# atmega_midi_x0x_heart.net
KiCad netlist of a schematic drawn in EAGLE
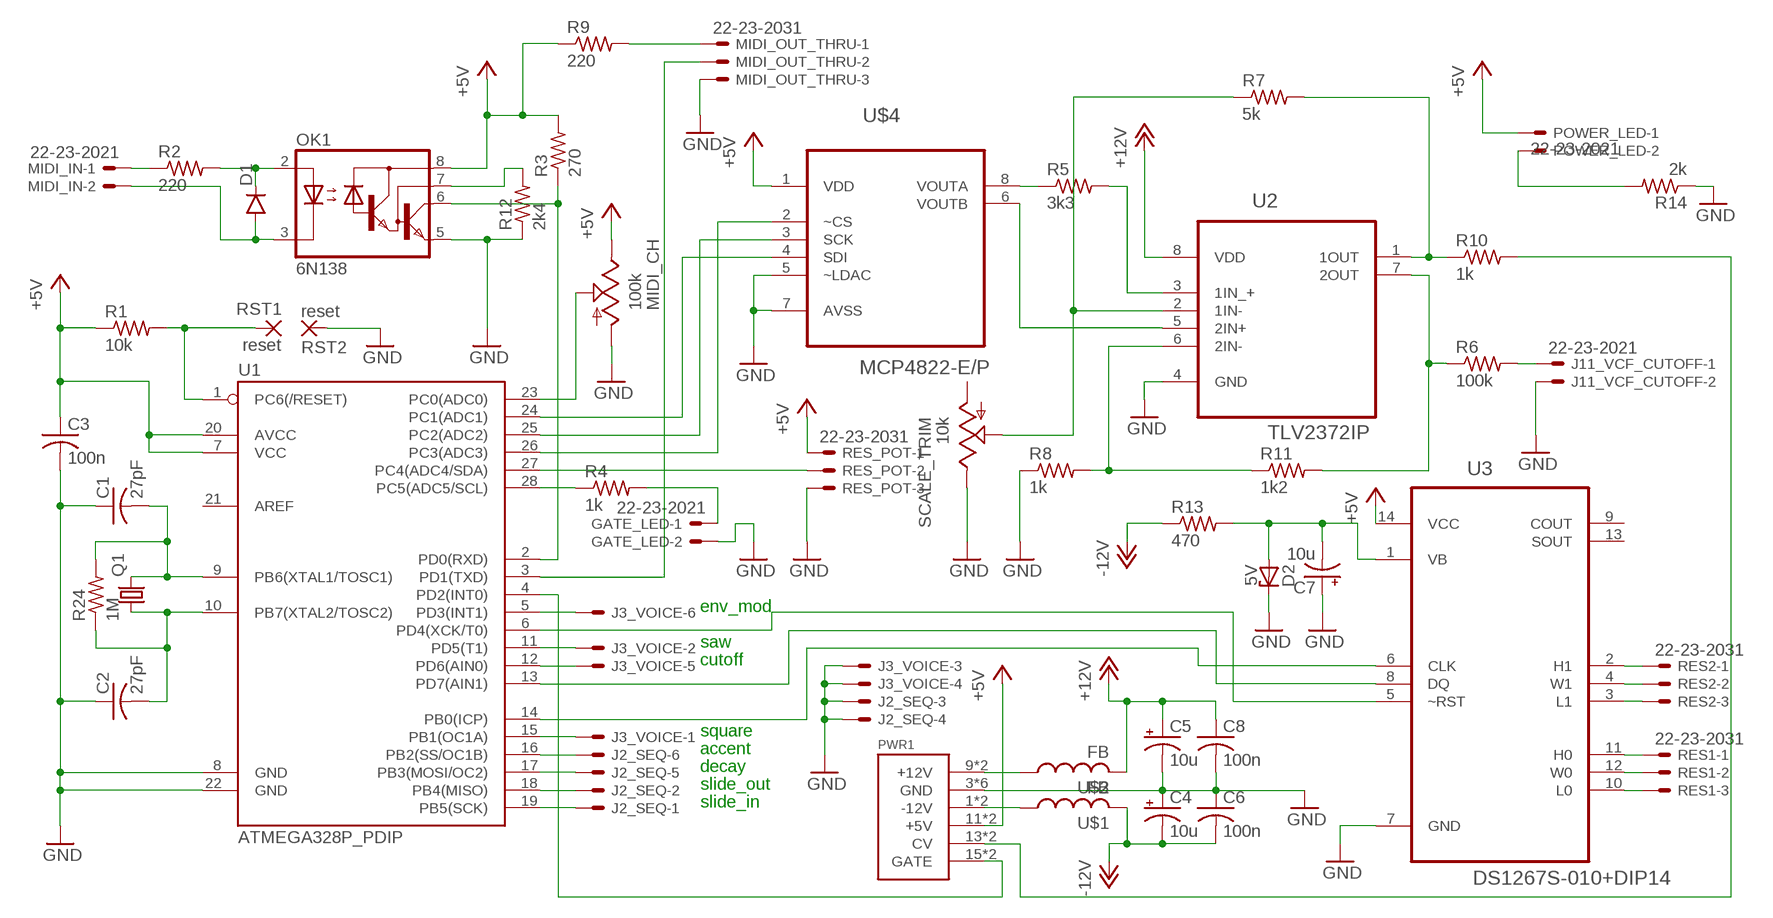
[diagram p0: schematic, sheet 1]

(export (version "E")
  (design (tool "Eeschema 10.0.6"))
  (components
    (comp (ref "C1")
      (value "27pF")
      (footprint "eagle-import:C050-024X044")
      (libsource (lib "eagle-import") (part "C-US050-024X044"))
    )
    (comp (ref "C2")
      (value "27pF")
      (footprint "eagle-import:C050-024X044")
      (libsource (lib "eagle-import") (part "C-US050-024X044"))
    )
    (comp (ref "C3")
      (value "100n")
      (footprint "eagle-import:C050-024X044")
      (libsource (lib "eagle-import") (part "C-US050-024X044"))
    )
    (comp (ref "C4")
      (value "10u")
      (footprint "eagle-import:B45181A")
      (libsource (lib "eagle-import") (part "CPOL-USB45181A"))
    )
    (comp (ref "C5")
      (value "10u")
      (footprint "eagle-import:B45181A")
      (libsource (lib "eagle-import") (part "CPOL-USB45181A"))
    )
    (comp (ref "C6")
      (value "100n")
      (footprint "eagle-import:C050-024X044")
      (libsource (lib "eagle-import") (part "C-US050-024X044"))
    )
    (comp (ref "C7")
      (value "10u")
      (footprint "eagle-import:B45181B")
      (libsource (lib "eagle-import") (part "CPOL-USB45181B"))
    )
    (comp (ref "C8")
      (value "100n")
      (footprint "eagle-import:C050-024X044")
      (libsource (lib "eagle-import") (part "C-US050-024X044"))
    )
    (comp (ref "D1")
      (value "DIODE1N4148")
      (footprint "eagle-import:DIODE-1N4148")
      (libsource (lib "eagle-import") (part "DIODE1N4148"))
    )
    (comp (ref "D2")
      (value "5V")
      (footprint "eagle-import:DO35Z10")
      (libsource (lib "eagle-import") (part "ZENER-DIODEDO35Z10"))
    )
    (comp (ref "GATE_LED")
      (value "22-23-2021")
      (footprint "eagle-import:22-23-2021")
      (fields (field (name "MF") "MOLEX"))
      (libsource (lib "eagle-import") (part "22-23-2021"))
    )
    (comp (ref "J2_SEQ")
      (value "22-23-2061")
      (footprint "eagle-import:22-23-2061")
      (fields (field (name "MF") "MOLEX"))
      (libsource (lib "eagle-import") (part "22-23-2061"))
    )
    (comp (ref "J3_VOICE")
      (value "22-23-2061")
      (footprint "eagle-import:22-23-2061")
      (fields (field (name "MF") "MOLEX"))
      (libsource (lib "eagle-import") (part "22-23-2061"))
    )
    (comp (ref "J11_VCF_CUTOFF")
      (value "22-23-2021")
      (footprint "eagle-import:22-23-2021")
      (fields (field (name "MF") "MOLEX"))
      (libsource (lib "eagle-import") (part "22-23-2021"))
    )
    (comp (ref "MIDI_CH")
      (value "100k")
      (footprint "eagle-import:B64W")
      (libsource (lib "eagle-import") (part "TRIM_US-B64W"))
    )
    (comp (ref "MIDI_IN")
      (value "22-23-2021")
      (footprint "eagle-import:22-23-2021")
      (fields (field (name "MF") "MOLEX"))
      (libsource (lib "eagle-import") (part "22-23-2021"))
    )
    (comp (ref "MIDI_OUT_THRU")
      (value "22-23-2031")
      (footprint "eagle-import:22-23-2031")
      (fields (field (name "MF") "MOLEX"))
      (libsource (lib "eagle-import") (part "22-23-2031"))
    )
    (comp (ref "OK1")
      (value "6N138")
      (footprint "eagle-import:DIL08")
      (fields (field (name "MF") "VISHAY/TELEFUNKEN"))
      (libsource (lib "eagle-import") (part "6N138"))
    )
    (comp (ref "POWER_LED")
      (value "22-23-2021")
      (footprint "eagle-import:22-23-2021")
      (fields (field (name "MF") "MOLEX"))
      (libsource (lib "eagle-import") (part "22-23-2021"))
    )
    (comp (ref "PWR1")
      (value "POWER")
      (footprint "eagle-import:POWER_16")
      (libsource (lib "eagle-import") (part "POWER"))
    )
    (comp (ref "Q1")
      (value "CRYSTALHC49S")
      (footprint "eagle-import:HC49_S")
      (libsource (lib "eagle-import") (part "CRYSTALHC49S"))
    )
    (comp (ref "R1")
      (value "10k")
      (footprint "eagle-import:0207_10")
      (libsource (lib "eagle-import") (part "R-US_0207/10"))
    )
    (comp (ref "R2")
      (value "220")
      (footprint "eagle-import:0207_10")
      (libsource (lib "eagle-import") (part "R-US_0207/10"))
    )
    (comp (ref "R3")
      (value "270")
      (footprint "eagle-import:0207_10")
      (libsource (lib "eagle-import") (part "R-US_0207/10"))
    )
    (comp (ref "R4")
      (value "1k")
      (footprint "eagle-import:0207_10")
      (libsource (lib "eagle-import") (part "R-US_0207/10"))
    )
    (comp (ref "R5")
      (value "3k3")
      (footprint "eagle-import:0207_10")
      (libsource (lib "eagle-import") (part "R-US_0207/10"))
    )
    (comp (ref "R6")
      (value "100k")
      (footprint "eagle-import:0207_10")
      (libsource (lib "eagle-import") (part "R-US_0207/10"))
    )
    (comp (ref "R7")
      (value "5k")
      (footprint "eagle-import:0207_10")
      (libsource (lib "eagle-import") (part "R-US_0207/10"))
    )
    (comp (ref "R8")
      (value "1k")
      (footprint "eagle-import:0207_10")
      (libsource (lib "eagle-import") (part "R-US_0207/10"))
    )
    (comp (ref "R9")
      (value "220")
      (footprint "eagle-import:0207_10")
      (libsource (lib "eagle-import") (part "R-US_0207/10"))
    )
    (comp (ref "R10")
      (value "1k")
      (footprint "eagle-import:0207_10")
      (libsource (lib "eagle-import") (part "R-US_0207/10"))
    )
    (comp (ref "R11")
      (value "1k2")
      (footprint "eagle-import:0207_10")
      (libsource (lib "eagle-import") (part "R-US_0207/10"))
    )
    (comp (ref "R12")
      (value "2k4")
      (footprint "eagle-import:0207_10")
      (libsource (lib "eagle-import") (part "R-US_0207/10"))
    )
    (comp (ref "R13")
      (value "470")
      (footprint "eagle-import:0207_10")
      (libsource (lib "eagle-import") (part "R-US_0207/10"))
    )
    (comp (ref "R14")
      (value "2k")
      (footprint "eagle-import:0207_10")
      (libsource (lib "eagle-import") (part "R-US_0207/10"))
    )
    (comp (ref "R24")
      (value "1M")
      (footprint "eagle-import:0207_10")
      (libsource (lib "eagle-import") (part "R-US_0207/10"))
    )
    (comp (ref "RES1")
      (value "22-23-2031")
      (footprint "eagle-import:22-23-2031")
      (fields (field (name "MF") "MOLEX"))
      (libsource (lib "eagle-import") (part "22-23-2031"))
    )
    (comp (ref "RES2")
      (value "22-23-2031")
      (footprint "eagle-import:22-23-2031")
      (fields (field (name "MF") "MOLEX"))
      (libsource (lib "eagle-import") (part "22-23-2031"))
    )
    (comp (ref "RES_POT")
      (value "22-23-2031")
      (footprint "eagle-import:22-23-2031")
      (fields (field (name "MF") "MOLEX"))
      (libsource (lib "eagle-import") (part "22-23-2031"))
    )
    (comp (ref "RST1")
      (value "reset")
      (footprint "eagle-import:2,54_0,9")
      (libsource (lib "eagle-import") (part "2,54/0,9"))
    )
    (comp (ref "RST2")
      (value "reset")
      (footprint "eagle-import:2,54_0,9")
      (libsource (lib "eagle-import") (part "2,54/0,9"))
    )
    (comp (ref "SCALE_TRIM")
      (value "10k")
      (footprint "eagle-import:B64W")
      (libsource (lib "eagle-import") (part "TRIM_US-B64W"))
    )
    (comp (ref "U$1") (value "FB") (footprint "eagle-import:FB") (libsource (lib "eagle-import") (part "FB")))
    (comp (ref "U$2") (value "FB") (footprint "eagle-import:FB") (libsource (lib "eagle-import") (part "FB")))
    (comp (ref "U$4")
      (value "MCP4822-E/P")
      (footprint "eagle-import:DIP254P762X432-8")
      (libsource (lib "eagle-import") (part "MCP4822-E/P"))
    )
    (comp (ref "U1")
      (value "ATMEGA328P_PDIP")
      (footprint "eagle-import:DIL28-3")
      (libsource (lib "eagle-import") (part "ATMEGA328P_PDIP"))
    )
    (comp (ref "U2")
      (value "TLV2372IP")
      (footprint "eagle-import:DIP254P762X508-8")
      (libsource (lib "eagle-import") (part "TLV2372IP"))
    )
    (comp (ref "U3")
      (value "DS1267S-010+DIP14")
      (footprint "eagle-import:DIP14")
      (libsource (lib "eagle-import") (part "DS1267S-010+DIP14"))
    )
  )
  (nets
    (net (code "1") (name "+5V") (class "Default")
      (node (ref "C3") (pin "1") (pinfunction "1_1") (pintype "passive"))
      (node (ref "MIDI_CH") (pin "E") (pinfunction "E_E") (pintype "passive"))
      (node (ref "OK1") (pin "8") (pinfunction "VCC_8") (pintype "passive"))
      (node (ref "POWER_LED") (pin "1") (pinfunction "S_1") (pintype "passive"))
      (node (ref "PWR1") (pin "11") (pinfunction "+5V_11") (pintype "bidirectional"))
      (node (ref "PWR1") (pin "12") (pinfunction "+5V_12") (pintype "bidirectional"))
      (node (ref "R1") (pin "1") (pinfunction "1_1") (pintype "passive"))
      (node (ref "R3") (pin "2") (pinfunction "2_2") (pintype "passive"))
      (node (ref "R9") (pin "1") (pinfunction "1_1") (pintype "passive"))
      (node (ref "RES_POT") (pin "1") (pinfunction "S_1") (pintype "passive"))
      (node (ref "U$4") (pin "1") (pinfunction "VDD_1") (pintype "power_in"))
      (node (ref "U1") (pin "20") (pinfunction "AVCC_20") (pintype "bidirectional"))
      (node (ref "U1") (pin "7") (pinfunction "VCC_7") (pintype "bidirectional"))
      (node (ref "U3") (pin "14") (pinfunction "VCC_14") (pintype "power_in"))
    )
    (net (code "2") (name "+12V") (class "Default")
      (node (ref "C5") (pin "+") (pinfunction "+_+") (pintype "passive"))
      (node (ref "C8") (pin "1") (pinfunction "1_1") (pintype "passive"))
      (node (ref "U$2") (pin "P$2") (pinfunction "2_P$2") (pintype "passive"))
      (node (ref "U2") (pin "8") (pinfunction "VDD_8") (pintype "power_in"))
    )
    (net (code "3") (name "-12V") (class "Default")
      (node (ref "C4") (pin "-") (pinfunction "-_-") (pintype "passive"))
      (node (ref "C6") (pin "2") (pinfunction "2_2") (pintype "passive"))
      (node (ref "R13") (pin "1") (pinfunction "1_1") (pintype "passive"))
      (node (ref "U$1") (pin "P$2") (pinfunction "2_P$2") (pintype "passive"))
    )
    (net (code "4") (name "GND") (class "Default")
      (node (ref "C1") (pin "1") (pinfunction "1_1") (pintype "passive"))
      (node (ref "C2") (pin "1") (pinfunction "1_1") (pintype "passive"))
      (node (ref "C3") (pin "2") (pinfunction "2_2") (pintype "passive"))
      (node (ref "C4") (pin "+") (pinfunction "+_+") (pintype "passive"))
      (node (ref "C5") (pin "-") (pinfunction "-_-") (pintype "passive"))
      (node (ref "C6") (pin "1") (pinfunction "1_1") (pintype "passive"))
      (node (ref "C7") (pin "+") (pinfunction "+_+") (pintype "passive"))
      (node (ref "C8") (pin "2") (pinfunction "2_2") (pintype "passive"))
      (node (ref "D2") (pin "C") (pinfunction "C_C") (pintype "passive"))
      (node (ref "GATE_LED") (pin "2") (pinfunction "S_2") (pintype "passive"))
      (node (ref "J11_VCF_CUTOFF") (pin "2") (pinfunction "S_2") (pintype "passive"))
      (node (ref "J2_SEQ") (pin "3") (pinfunction "S_3") (pintype "passive"))
      (node (ref "J2_SEQ") (pin "4") (pinfunction "S_4") (pintype "passive"))
      (node (ref "J3_VOICE") (pin "3") (pinfunction "S_3") (pintype "passive"))
      (node (ref "J3_VOICE") (pin "4") (pinfunction "S_4") (pintype "passive"))
      (node (ref "MIDI_CH") (pin "A") (pinfunction "A_A") (pintype "passive"))
      (node (ref "MIDI_OUT_THRU") (pin "3") (pinfunction "S_3") (pintype "passive"))
      (node (ref "OK1") (pin "5") (pinfunction "GND_5") (pintype "passive"))
      (node (ref "PWR1") (pin "3") (pinfunction "GND_3") (pintype "bidirectional"))
      (node (ref "PWR1") (pin "4") (pinfunction "GND_4") (pintype "bidirectional"))
      (node (ref "PWR1") (pin "5") (pinfunction "GND_5") (pintype "bidirectional"))
      (node (ref "PWR1") (pin "6") (pinfunction "GND_6") (pintype "bidirectional"))
      (node (ref "PWR1") (pin "7") (pinfunction "GND_7") (pintype "bidirectional"))
      (node (ref "PWR1") (pin "8") (pinfunction "GND_8") (pintype "bidirectional"))
      (node (ref "R12") (pin "1") (pinfunction "1_1") (pintype "passive"))
      (node (ref "R14") (pin "1") (pinfunction "1_1") (pintype "passive"))
      (node (ref "R8") (pin "1") (pinfunction "1_1") (pintype "passive"))
      (node (ref "RES_POT") (pin "3") (pinfunction "S_3") (pintype "passive"))
      (node (ref "RST2") (pin "1") (pinfunction "P_1") (pintype "passive"))
      (node (ref "SCALE_TRIM") (pin "E") (pinfunction "E_E") (pintype "passive"))
      (node (ref "U$4") (pin "5") (pinfunction "~{LDAC}_5") (pintype "input"))
      (node (ref "U$4") (pin "7") (pinfunction "AVSS_7") (pintype "passive"))
      (node (ref "U1") (pin "22") (pinfunction "GND_22") (pintype "bidirectional"))
      (node (ref "U1") (pin "8") (pinfunction "GND_8") (pintype "bidirectional"))
      (node (ref "U2") (pin "4") (pinfunction "GND_4") (pintype "passive"))
      (node (ref "U3") (pin "7") (pinfunction "GND_7") (pintype "passive"))
    )
    (net (code "5") (name "Net-(GATE_LEDA-S)") (class "Default")
      (node (ref "GATE_LED") (pin "1") (pinfunction "S_1") (pintype "passive"))
      (node (ref "R4") (pin "2") (pinfunction "2_2") (pintype "passive"))
    )
    (net (code "6") (name "Net-(J2_SEQA-S)") (class "Default")
      (node (ref "J2_SEQ") (pin "1") (pinfunction "S_1") (pintype "passive"))
      (node (ref "U1") (pin "19") (pinfunction "PB5(SCK)_19") (pintype "bidirectional"))
    )
    (net (code "7") (name "Net-(J2_SEQB-S)") (class "Default")
      (node (ref "J2_SEQ") (pin "2") (pinfunction "S_2") (pintype "passive"))
      (node (ref "U1") (pin "18") (pinfunction "PB4(MISO)_18") (pintype "bidirectional"))
    )
    (net (code "8") (name "Net-(J2_SEQE-S)") (class "Default")
      (node (ref "J2_SEQ") (pin "5") (pinfunction "S_5") (pintype "passive"))
      (node (ref "U1") (pin "17") (pinfunction "PB3(MOSI/OC2)_17") (pintype "bidirectional"))
    )
    (net (code "9") (name "Net-(J2_SEQF-S)") (class "Default")
      (node (ref "J2_SEQ") (pin "6") (pinfunction "S_6") (pintype "passive"))
      (node (ref "U1") (pin "16") (pinfunction "PB2(SS/OC1B)_16") (pintype "bidirectional"))
    )
    (net (code "10") (name "Net-(J3_VOICEA-S)") (class "Default")
      (node (ref "J3_VOICE") (pin "1") (pinfunction "S_1") (pintype "passive"))
      (node (ref "U1") (pin "15") (pinfunction "PB1(OC1A)_15") (pintype "bidirectional"))
    )
    (net (code "11") (name "Net-(J3_VOICEB-S)") (class "Default")
      (node (ref "J3_VOICE") (pin "2") (pinfunction "S_2") (pintype "passive"))
      (node (ref "U1") (pin "11") (pinfunction "PD5(T1)_11") (pintype "bidirectional"))
    )
    (net (code "12") (name "Net-(J3_VOICEE-S)") (class "Default")
      (node (ref "J3_VOICE") (pin "5") (pinfunction "S_5") (pintype "passive"))
      (node (ref "U1") (pin "12") (pinfunction "PD6(AIN0)_12") (pintype "bidirectional"))
    )
    (net (code "13") (name "Net-(J3_VOICEF-S)") (class "Default")
      (node (ref "J3_VOICE") (pin "6") (pinfunction "S_6") (pintype "passive"))
      (node (ref "U1") (pin "5") (pinfunction "PD3(INT1)_5") (pintype "bidirectional"))
    )
    (net (code "14") (name "Net-(J11_VCF_CUTOFFA-S)") (class "Default")
      (node (ref "J11_VCF_CUTOFF") (pin "1") (pinfunction "S_1") (pintype "passive"))
      (node (ref "R6") (pin "2") (pinfunction "2_2") (pintype "passive"))
    )
    (net (code "15") (name "Net-(MIDI_INA-S)") (class "Default")
      (node (ref "MIDI_IN") (pin "1") (pinfunction "S_1") (pintype "passive"))
      (node (ref "R2") (pin "1") (pinfunction "1_1") (pintype "passive"))
    )
    (net (code "16") (name "Net-(MIDI_INB-S)") (class "Default")
      (node (ref "D1") (pin "A") (pinfunction "A_A") (pintype "passive"))
      (node (ref "MIDI_IN") (pin "2") (pinfunction "S_2") (pintype "passive"))
      (node (ref "OK1") (pin "3") (pinfunction "C_3") (pintype "passive"))
    )
    (net (code "17") (name "Net-(MIDI_OUT_THRUA-S)") (class "Default")
      (node (ref "MIDI_OUT_THRU") (pin "1") (pinfunction "S_1") (pintype "passive"))
      (node (ref "R9") (pin "2") (pinfunction "2_2") (pintype "passive"))
    )
    (net (code "18") (name "Net-(MIDI_OUT_THRUB-S)") (class "Default")
      (node (ref "MIDI_OUT_THRU") (pin "2") (pinfunction "S_2") (pintype "passive"))
      (node (ref "U1") (pin "3") (pinfunction "PD1(TXD)_3") (pintype "bidirectional"))
    )
    (net (code "19") (name "Net-(OK1-A)") (class "Default")
      (node (ref "D1") (pin "C") (pinfunction "C_C") (pintype "passive"))
      (node (ref "OK1") (pin "2") (pinfunction "A_2") (pintype "passive"))
      (node (ref "R2") (pin "2") (pinfunction "2_2") (pintype "passive"))
    )
    (net (code "20") (name "Net-(OK1-VB)") (class "Default")
      (node (ref "OK1") (pin "7") (pinfunction "VB_7") (pintype "passive"))
      (node (ref "R12") (pin "2") (pinfunction "2_2") (pintype "passive"))
    )
    (net (code "21") (name "Net-(OK1-VO)") (class "Default")
      (node (ref "OK1") (pin "6") (pinfunction "VO_6") (pintype "passive"))
      (node (ref "R3") (pin "1") (pinfunction "1_1") (pintype "passive"))
      (node (ref "U1") (pin "2") (pinfunction "PD0(RXD)_2") (pintype "bidirectional"))
    )
    (net (code "22") (name "Net-(POWER_LEDB-S)") (class "Default")
      (node (ref "POWER_LED") (pin "2") (pinfunction "S_2") (pintype "passive"))
      (node (ref "R14") (pin "2") (pinfunction "2_2") (pintype "passive"))
    )
    (net (code "23") (name "Net-(PWR1-CV-Pad13)") (class "Default")
      (node (ref "PWR1") (pin "13") (pinfunction "CV_13") (pintype "bidirectional"))
      (node (ref "PWR1") (pin "14") (pinfunction "CV_14") (pintype "bidirectional"))
      (node (ref "R10") (pin "2") (pinfunction "2_2") (pintype "passive"))
    )
    (net (code "24") (name "Net-(RES1A-S)") (class "Default")
      (node (ref "RES1") (pin "1") (pinfunction "S_1") (pintype "passive"))
      (node (ref "U3") (pin "11") (pinfunction "H0_11") (pintype "passive"))
    )
    (net (code "25") (name "Net-(RES1B-S)") (class "Default")
      (node (ref "RES1") (pin "2") (pinfunction "S_2") (pintype "passive"))
      (node (ref "U3") (pin "12") (pinfunction "W0_12") (pintype "passive"))
    )
    (net (code "26") (name "Net-(RES1C-S)") (class "Default")
      (node (ref "RES1") (pin "3") (pinfunction "S_3") (pintype "passive"))
      (node (ref "U3") (pin "10") (pinfunction "L0_10") (pintype "passive"))
    )
    (net (code "27") (name "Net-(RES2A-S)") (class "Default")
      (node (ref "RES2") (pin "1") (pinfunction "S_1") (pintype "passive"))
      (node (ref "U3") (pin "2") (pinfunction "H1_2") (pintype "passive"))
    )
    (net (code "28") (name "Net-(RES2B-S)") (class "Default")
      (node (ref "RES2") (pin "2") (pinfunction "S_2") (pintype "passive"))
      (node (ref "U3") (pin "4") (pinfunction "W1_4") (pintype "passive"))
    )
    (net (code "29") (name "Net-(RES2C-S)") (class "Default")
      (node (ref "RES2") (pin "3") (pinfunction "S_3") (pintype "passive"))
      (node (ref "U3") (pin "3") (pinfunction "L1_3") (pintype "passive"))
    )
    (net (code "30") (name "Net-(RES_POTB-S)") (class "Default")
      (node (ref "RES_POT") (pin "2") (pinfunction "S_2") (pintype "passive"))
      (node (ref "U1") (pin "27") (pinfunction "PC4(ADC4/SDA)_27") (pintype "bidirectional"))
    )
    (net (code "31") (name "Net-(RST1-P)") (class "Default")
      (node (ref "R1") (pin "2") (pinfunction "2_2") (pintype "passive"))
      (node (ref "RST1") (pin "1") (pinfunction "P_1") (pintype "passive"))
      (node (ref "U1") (pin "1") (pinfunction "PC6(/RESET)_1") (pintype "bidirectional"))
    )
    (net (code "32") (name "Net-(U$1-1)") (class "Default")
      (node (ref "PWR1") (pin "1") (pinfunction "-12V_1") (pintype "bidirectional"))
      (node (ref "PWR1") (pin "2") (pinfunction "-12V_2") (pintype "bidirectional"))
      (node (ref "U$1") (pin "P$1") (pinfunction "1_P$1") (pintype "passive"))
    )
    (net (code "33") (name "Net-(U$2-1)") (class "Default")
      (node (ref "PWR1") (pin "10") (pinfunction "+12V_10") (pintype "bidirectional"))
      (node (ref "PWR1") (pin "9") (pinfunction "+12V_9") (pintype "bidirectional"))
      (node (ref "U$2") (pin "P$1") (pinfunction "1_P$1") (pintype "passive"))
    )
    (net (code "34") (name "Net-(U$4-SCK)") (class "Default")
      (node (ref "U$4") (pin "3") (pinfunction "SCK_3") (pintype "input"))
      (node (ref "U1") (pin "25") (pinfunction "PC2(ADC2)_25") (pintype "bidirectional"))
    )
    (net (code "35") (name "Net-(U$4-SDI)") (class "Default")
      (node (ref "U$4") (pin "4") (pinfunction "SDI_4") (pintype "input"))
      (node (ref "U1") (pin "24") (pinfunction "PC1(ADC1)_24") (pintype "bidirectional"))
    )
    (net (code "36") (name "Net-(U$4-VOUTA)") (class "Default")
      (node (ref "R5") (pin "1") (pinfunction "1_1") (pintype "passive"))
      (node (ref "U$4") (pin "8") (pinfunction "VOUTA_8") (pintype "output"))
    )
    (net (code "37") (name "Net-(U$4-VOUTB)") (class "Default")
      (node (ref "U$4") (pin "6") (pinfunction "VOUTB_6") (pintype "output"))
      (node (ref "U2") (pin "5") (pinfunction "2IN+_5") (pintype "input"))
    )
    (net (code "38") (name "Net-(U$4-~{CS})") (class "Default")
      (node (ref "U$4") (pin "2") (pinfunction "~{CS}_2") (pintype "input"))
      (node (ref "U1") (pin "26") (pinfunction "PC3(ADC3)_26") (pintype "bidirectional"))
    )
    (net (code "39") (name "Net-(U1-PB0(ICP))") (class "Default")
      (node (ref "U1") (pin "14") (pinfunction "PB0(ICP)_14") (pintype "bidirectional"))
      (node (ref "U3") (pin "6") (pinfunction "CLK_6") (pintype "input"))
    )
    (net (code "40") (name "Net-(U1-PB6(XTAL1{slash}TOSC1))") (class "Default")
      (node (ref "C1") (pin "2") (pinfunction "2_2") (pintype "passive"))
      (node (ref "Q1") (pin "2") (pinfunction "2_2") (pintype "passive"))
      (node (ref "R24") (pin "2") (pinfunction "2_2") (pintype "passive"))
      (node (ref "U1") (pin "9") (pinfunction "PB6(XTAL1/TOSC1)_9") (pintype "bidirectional"))
    )
    (net (code "41") (name "Net-(U1-PB7(XTAL2{slash}TOSC2))") (class "Default")
      (node (ref "C2") (pin "2") (pinfunction "2_2") (pintype "passive"))
      (node (ref "Q1") (pin "1") (pinfunction "1_1") (pintype "passive"))
      (node (ref "R24") (pin "1") (pinfunction "1_1") (pintype "passive"))
      (node (ref "U1") (pin "10") (pinfunction "PB7(XTAL2/TOSC2)_10") (pintype "bidirectional"))
    )
    (net (code "42") (name "Net-(U1-PC0(ADC0))") (class "Default")
      (node (ref "MIDI_CH") (pin "S") (pinfunction "S_S") (pintype "passive"))
      (node (ref "U1") (pin "23") (pinfunction "PC0(ADC0)_23") (pintype "bidirectional"))
    )
    (net (code "43") (name "Net-(U1-PC5(ADC5{slash}SCL))") (class "Default")
      (node (ref "R4") (pin "1") (pinfunction "1_1") (pintype "passive"))
      (node (ref "U1") (pin "28") (pinfunction "PC5(ADC5/SCL)_28") (pintype "bidirectional"))
    )
    (net (code "44") (name "Net-(U1-PD2(INT0))") (class "Default")
      (node (ref "PWR1") (pin "15") (pinfunction "GATE_15") (pintype "bidirectional"))
      (node (ref "PWR1") (pin "16") (pinfunction "GATE_16") (pintype "bidirectional"))
      (node (ref "U1") (pin "4") (pinfunction "PD2(INT0)_4") (pintype "bidirectional"))
    )
    (net (code "45") (name "Net-(U1-PD4(XCK{slash}T0))") (class "Default")
      (node (ref "U1") (pin "6") (pinfunction "PD4(XCK/T0)_6") (pintype "bidirectional"))
      (node (ref "U3") (pin "5") (pinfunction "~{RST}_5") (pintype "input"))
    )
    (net (code "46") (name "Net-(U1-PD7(AIN1))") (class "Default")
      (node (ref "U1") (pin "13") (pinfunction "PD7(AIN1)_13") (pintype "bidirectional"))
      (node (ref "U3") (pin "8") (pinfunction "DQ_8") (pintype "input"))
    )
    (net (code "47") (name "Net-(U2-1IN-)") (class "Default")
      (node (ref "R7") (pin "1") (pinfunction "1_1") (pintype "passive"))
      (node (ref "SCALE_TRIM") (pin "S") (pinfunction "S_S") (pintype "passive"))
      (node (ref "U2") (pin "2") (pinfunction "1IN-_2") (pintype "input"))
    )
    (net (code "48") (name "Net-(U2-1IN_+)") (class "Default")
      (node (ref "R5") (pin "2") (pinfunction "2_2") (pintype "passive"))
      (node (ref "U2") (pin "3") (pinfunction "1IN_+_3") (pintype "input"))
    )
    (net (code "49") (name "Net-(U2-1OUT)") (class "Default")
      (node (ref "R10") (pin "1") (pinfunction "1_1") (pintype "passive"))
      (node (ref "R7") (pin "2") (pinfunction "2_2") (pintype "passive"))
      (node (ref "U2") (pin "1") (pinfunction "1OUT_1") (pintype "output"))
    )
    (net (code "50") (name "Net-(U2-2IN-)") (class "Default")
      (node (ref "R11") (pin "1") (pinfunction "1_1") (pintype "passive"))
      (node (ref "R8") (pin "2") (pinfunction "2_2") (pintype "passive"))
      (node (ref "U2") (pin "6") (pinfunction "2IN-_6") (pintype "input"))
    )
    (net (code "51") (name "Net-(U2-2OUT)") (class "Default")
      (node (ref "R11") (pin "2") (pinfunction "2_2") (pintype "passive"))
      (node (ref "R6") (pin "1") (pinfunction "1_1") (pintype "passive"))
      (node (ref "U2") (pin "7") (pinfunction "2OUT_7") (pintype "output"))
    )
    (net (code "52") (name "Net-(U3-VB)") (class "Default")
      (node (ref "C7") (pin "-") (pinfunction "-_-") (pintype "passive"))
      (node (ref "D2") (pin "A") (pinfunction "A_A") (pintype "passive"))
      (node (ref "R13") (pin "2") (pinfunction "2_2") (pintype "passive"))
      (node (ref "U3") (pin "1") (pinfunction "VB_1") (pintype "input"))
    )
    (net (code "53") (name "unconnected-(SCALE_TRIM-PadA)") (class "Default")
      (node (ref "SCALE_TRIM") (pin "A") (pinfunction "A_A") (pintype "passive"))
    )
    (net (code "54") (name "unconnected-(U1-AREF-Pad21)") (class "Default")
      (node (ref "U1") (pin "21") (pinfunction "AREF_21") (pintype "bidirectional"))
    )
    (net (code "55") (name "unconnected-(U3-COUT-Pad9)") (class "Default")
      (node (ref "U3") (pin "9") (pinfunction "COUT_9") (pintype "output"))
    )
    (net (code "56") (name "unconnected-(U3-SOUT-Pad13)") (class "Default")
      (node (ref "U3") (pin "13") (pinfunction "SOUT_13") (pintype "output"))
    )
  )
)
